# SmartMailbox.net
KiCad netlist of a schematic drawn in EAGLE
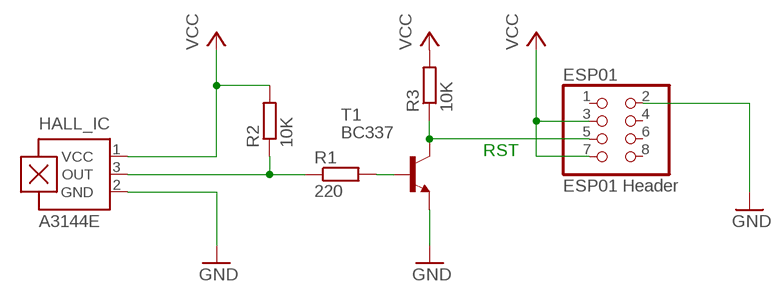
[diagram p0: schematic, sheet 1]

(export (version "E")
  (design (tool "Eeschema 10.0.6"))
  (components
    (comp (ref "ESP01")
      (value "ESP01 Header")
      (footprint "eagle-import:2X04")
      (libsource (lib "eagle-import") (part "PINHD-2X4"))
    )
    (comp (ref "HALL_IC")
      (value "A3144E")
      (footprint "eagle-import:SIP3-UA")
      (fields (field (name "MF") "ALLEGRO MICROSYSTEMS, INC.") (field (name "MPN") "A1301EUA-T"))
      (libsource (lib "eagle-import") (part "A13?UA01"))
    )
    (comp (ref "R1")
      (value "220")
      (footprint "eagle-import:0204V")
      (libsource (lib "eagle-import") (part "R-EU_0204/2V"))
    )
    (comp (ref "R2")
      (value "10K")
      (footprint "eagle-import:0204V")
      (libsource (lib "eagle-import") (part "R-EU_0204/2V"))
    )
    (comp (ref "R3")
      (value "10K")
      (footprint "eagle-import:0204V")
      (libsource (lib "eagle-import") (part "R-EU_0204/2V"))
    )
    (comp (ref "T1")
      (value "BC337")
      (footprint "eagle-import:TO92-EBC-OVAL")
      (libsource (lib "eagle-import") (part "2N2222"))
    )
  )
  (nets
    (net (code "1") (name "GND") (class "Default")
      (node (ref "ESP01") (pin "2") (pinfunction "2_2") (pintype "passive"))
      (node (ref "HALL_IC") (pin "2") (pinfunction "GND_2") (pintype "power_in"))
      (node (ref "T1") (pin "E") (pinfunction "E_E") (pintype "passive"))
    )
    (net (code "2") (name "Net-(ESP01-Pad5)") (class "Default")
      (node (ref "ESP01") (pin "5") (pinfunction "5_5") (pintype "passive"))
      (node (ref "R3") (pin "1") (pinfunction "1_1") (pintype "passive"))
      (node (ref "T1") (pin "C") (pinfunction "C_C") (pintype "passive"))
    )
    (net (code "3") (name "Net-(HALL_IC-OUT)") (class "Default")
      (node (ref "HALL_IC") (pin "3") (pinfunction "OUT_3") (pintype "output"))
      (node (ref "R1") (pin "1") (pinfunction "1_1") (pintype "passive"))
      (node (ref "R2") (pin "1") (pinfunction "1_1") (pintype "passive"))
    )
    (net (code "4") (name "Net-(R1-Pad2)") (class "Default")
      (node (ref "R1") (pin "2") (pinfunction "2_2") (pintype "passive"))
      (node (ref "T1") (pin "B") (pinfunction "B_B") (pintype "passive"))
    )
    (net (code "5") (name "VCC") (class "Default")
      (node (ref "ESP01") (pin "3") (pinfunction "3_3") (pintype "passive"))
      (node (ref "ESP01") (pin "7") (pinfunction "7_7") (pintype "passive"))
      (node (ref "HALL_IC") (pin "1") (pinfunction "VCC_1") (pintype "power_in"))
      (node (ref "R2") (pin "2") (pinfunction "2_2") (pintype "passive"))
      (node (ref "R3") (pin "2") (pinfunction "2_2") (pintype "passive"))
    )
    (net (code "6") (name "unconnected-(ESP01-Pad1)") (class "Default")
      (node (ref "ESP01") (pin "1") (pinfunction "1_1") (pintype "passive"))
    )
    (net (code "7") (name "unconnected-(ESP01-Pad4)") (class "Default")
      (node (ref "ESP01") (pin "4") (pinfunction "4_4") (pintype "passive"))
    )
    (net (code "8") (name "unconnected-(ESP01-Pad6)") (class "Default")
      (node (ref "ESP01") (pin "6") (pinfunction "6_6") (pintype "passive"))
    )
    (net (code "9") (name "unconnected-(ESP01-Pad8)") (class "Default")
      (node (ref "ESP01") (pin "8") (pinfunction "8_8") (pintype "passive"))
    )
  )
)
